# SCH_RK86_power_2024-10-30.net
KiCad netlist of a schematic drawn in EasyEDA
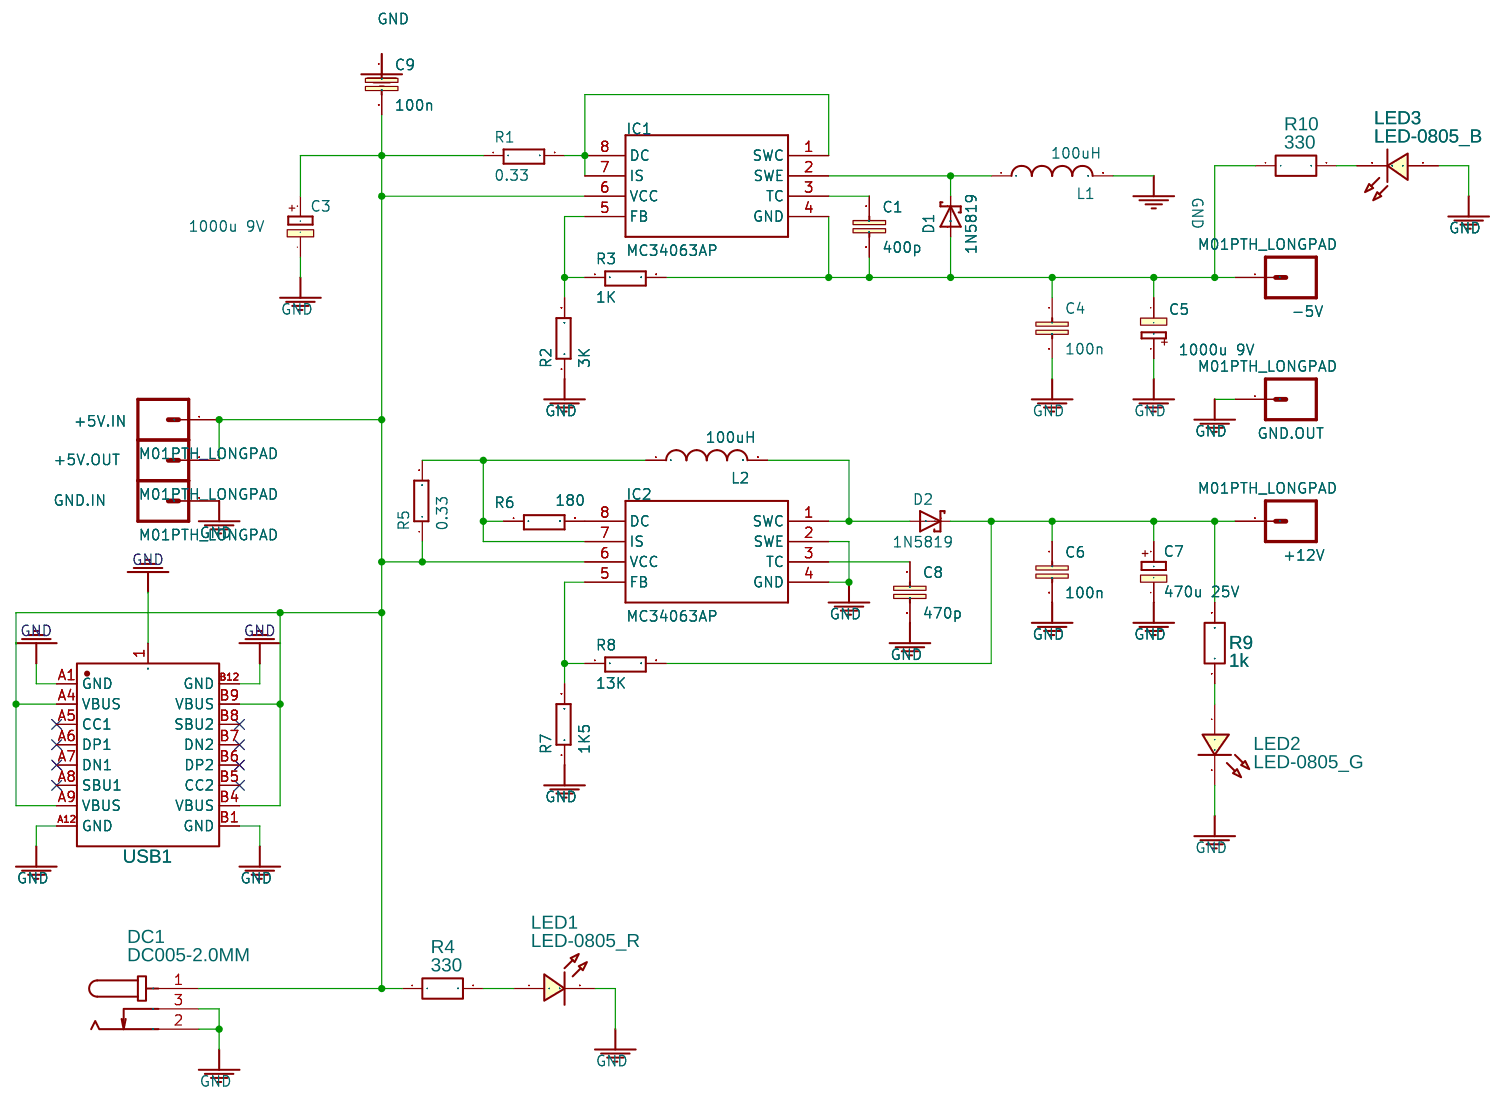
[diagram p0: schematic sheet]

(export (version "E")
  (design (tool "Eeschema 10.0.6"))
  (components
    (comp (ref "+5V.IN") (value "M01PTH_LONGPAD") (libsource (lib "") (part "Unknown_-110_-160")))
    (comp (ref "+5V.OUT") (value "M01PTH_LONGPAD") (libsource (lib "") (part "Unknown_-110_-140")))
    (comp (ref "+12V") (value "M01PTH_LONGPAD") (libsource (lib "") (part "Unknown_450_-110")))
    (comp (ref "-5V") (value "M01PTH_LONGPAD") (libsource (lib "") (part "Unknown_450_-230")))
    (comp (ref "C1") (value "400p") (libsource (lib "") (part "Unknown_240_-260")))
    (comp (ref "C3") (value "1000u 9V") (libsource (lib "") (part "Unknown_-40_-260")))
    (comp (ref "C4") (value "100n") (libsource (lib "") (part "Unknown_330_-210")))
    (comp (ref "C5") (value "1000u 9V") (libsource (lib "") (part "Unknown_380_-200")))
    (comp (ref "C6") (value "100n") (libsource (lib "") (part "Unknown_330_-90")))
    (comp (ref "C7") (value "470u 25V") (libsource (lib "") (part "Unknown_380_-90")))
    (comp (ref "C8") (value "470p") (libsource (lib "") (part "Unknown_260_-80")))
    (comp (ref "C9") (value "100n") (libsource (lib "") (part "Unknown_0_-330")))
    (comp (ref "D1") (value "1N5819") (libsource (lib "") (part "Unknown_280_-260")))
    (comp (ref "D2") (value "1N5819") (libsource (lib "") (part "Unknown_270_-110")))
    (comp (ref "DC1")
      (value "DC005-2.0MM")
      (fields (field (name "Manufacturer Part") "DC005-T20") (field (name "Manufacturer") "SOFNG(硕方)"))
      (libsource (lib "") (part "DC005-2.0MM"))
    )
    (comp (ref "GND.IN") (value "M01PTH_LONGPAD") (libsource (lib "") (part "Unknown_-110_-120")))
    (comp (ref "GND.OUT") (value "M01PTH_LONGPAD") (libsource (lib "") (part "Unknown_450_-170")))
    (comp (ref "IC1") (value "MC34063AP") (libsource (lib "") (part "Unknown_160_-290")))
    (comp (ref "IC2") (value "MC34063AP") (libsource (lib "") (part "Unknown_160_-110")))
    (comp (ref "L1") (value "100uH") (libsource (lib "") (part "Unknown_330_-280")))
    (comp (ref "L2") (value "100uH") (libsource (lib "") (part "Unknown_160_-140")))
    (comp (ref "LED1")
      (value "LED-0805_R")
      (fields
        (field (name "Manufacturer Part") "17-21SURC/S530-A3/TR8")
        (field (name "Manufacturer") "EVERLIGHT(台湾亿光)")
      )
      (libsource (lib "") (part "LED-0805_R"))
    )
    (comp (ref "LED2")
      (value "LED-0805_G")
      (fields (field (name "Manufacturer Part") "NCD0805G1") (field (name "Manufacturer") "国星光电"))
      (libsource (lib "") (part "LED-0805_G"))
    )
    (comp (ref "LED3")
      (value "LED-0805_B")
      (fields (field (name "Manufacturer Part") "D-B080508B1-KS2") (field (name "Manufacturer") "方舟 ARKLED"))
      (libsource (lib "") (part "LED-0805_B"))
    )
    (comp (ref "R1") (value "0.33") (libsource (lib "") (part "Unknown_70_-290")))
    (comp (ref "R2") (value "3K") (libsource (lib "") (part "Unknown_90_-200")))
    (comp (ref "R3") (value "1K") (libsource (lib "") (part "Unknown_120_-230")))
    (comp (ref "R4") (value "330") (libsource (lib "") (part "R_0805_EU_1")))
    (comp (ref "R5") (value "0.33") (libsource (lib "") (part "Unknown_20_-120")))
    (comp (ref "R6") (value "180") (libsource (lib "") (part "Unknown_80_-110")))
    (comp (ref "R7") (value "1K5") (libsource (lib "") (part "Unknown_90_-10")))
    (comp (ref "R8") (value "13K") (libsource (lib "") (part "Unknown_120_-40")))
    (comp (ref "R9") (value "1k") (libsource (lib "") (part "R_0805_EU")))
    (comp (ref "R10") (value "330") (libsource (lib "") (part "R_1206_EU")))
    (comp (ref "USB1")
      (value "TYPE-C-2.0-16PIN-SMT-3")
      (fields (field (name "Manufacturer") "CIKI(皓富)"))
      (libsource (lib "") (part "TYPE-C-2.0-16PIN-SMT-3"))
    )
  )
  (nets
    (net (code "1") (name "GND") (class "Default")
      (node (ref "C3") (pin "-") (pinfunction "-_-") (pintype "bidirectional"))
      (node (ref "C4") (pin "2") (pinfunction "2_2") (pintype "bidirectional"))
      (node (ref "C5") (pin "+") (pinfunction "+_+") (pintype "bidirectional"))
      (node (ref "C6") (pin "2") (pinfunction "2_2") (pintype "bidirectional"))
      (node (ref "C7") (pin "-") (pinfunction "-_-") (pintype "bidirectional"))
      (node (ref "C8") (pin "2") (pinfunction "2_2") (pintype "bidirectional"))
      (node (ref "C9") (pin "1") (pinfunction "1_1") (pintype "bidirectional"))
      (node (ref "DC1") (pin "2") (pinfunction "2_2") (pintype "unspecified"))
      (node (ref "DC1") (pin "3") (pinfunction "3_3") (pintype "unspecified"))
      (node (ref "GND.IN") (pin "1") (pinfunction "1_1") (pintype "bidirectional"))
      (node (ref "GND.OUT") (pin "1") (pinfunction "1_1") (pintype "bidirectional"))
      (node (ref "IC2") (pin "2") (pinfunction "SWE_2") (pintype "bidirectional"))
      (node (ref "IC2") (pin "4") (pinfunction "GND_4") (pintype "bidirectional"))
      (node (ref "L1") (pin "2") (pinfunction "2_2") (pintype "bidirectional"))
      (node (ref "LED1") (pin "2") (pinfunction "2_2") (pintype "unspecified"))
      (node (ref "LED2") (pin "2") (pinfunction "2_2") (pintype "unspecified"))
      (node (ref "LED3") (pin "1") (pinfunction "1_1") (pintype "unspecified"))
      (node (ref "R2") (pin "1") (pinfunction "1_1") (pintype "bidirectional"))
      (node (ref "R7") (pin "1") (pinfunction "1_1") (pintype "bidirectional"))
      (node (ref "USB1") (pin "1") (pinfunction "EH_1") (pintype "unspecified"))
      (node (ref "USB1") (pin "A1") (pinfunction "GND_A1") (pintype "unspecified"))
      (node (ref "USB1") (pin "A12") (pinfunction "GND_A12") (pintype "unspecified"))
      (node (ref "USB1") (pin "B1") (pinfunction "GND_B1") (pintype "unspecified"))
      (node (ref "USB1") (pin "B12") (pinfunction "GND_B12") (pintype "unspecified"))
    )
    (net (code "2") (name "Net-(D1-A)") (class "Default")
      (node (ref "-5V") (pin "1") (pinfunction "1_1") (pintype "bidirectional"))
      (node (ref "C1") (pin "2") (pinfunction "2_2") (pintype "bidirectional"))
      (node (ref "C4") (pin "1") (pinfunction "1_1") (pintype "bidirectional"))
      (node (ref "C5") (pin "-") (pinfunction "-_-") (pintype "bidirectional"))
      (node (ref "D1") (pin "1") (pinfunction "A_1") (pintype "bidirectional"))
      (node (ref "IC1") (pin "4") (pinfunction "GND_4") (pintype "bidirectional"))
      (node (ref "R10") (pin "1") (pinfunction "1_1") (pintype "unspecified"))
      (node (ref "R3") (pin "2") (pinfunction "2_2") (pintype "bidirectional"))
    )
    (net (code "3") (name "Net-(D1-C)") (class "Default")
      (node (ref "D1") (pin "2") (pinfunction "C_2") (pintype "bidirectional"))
      (node (ref "IC1") (pin "2") (pinfunction "SWE_2") (pintype "bidirectional"))
      (node (ref "L1") (pin "1") (pinfunction "1_1") (pintype "bidirectional"))
    )
    (net (code "4") (name "Net-(D2-A)") (class "Default")
      (node (ref "D2") (pin "1") (pinfunction "A_1") (pintype "bidirectional"))
      (node (ref "IC2") (pin "1") (pinfunction "SWC_1") (pintype "bidirectional"))
      (node (ref "L2") (pin "2") (pinfunction "2_2") (pintype "bidirectional"))
    )
    (net (code "5") (name "Net-(D2-C)") (class "Default")
      (node (ref "+12V") (pin "1") (pinfunction "1_1") (pintype "bidirectional"))
      (node (ref "C6") (pin "1") (pinfunction "1_1") (pintype "bidirectional"))
      (node (ref "C7") (pin "+") (pinfunction "+_+") (pintype "bidirectional"))
      (node (ref "D2") (pin "2") (pinfunction "C_2") (pintype "bidirectional"))
      (node (ref "R8") (pin "2") (pinfunction "2_2") (pintype "bidirectional"))
      (node (ref "R9") (pin "2") (pinfunction "2_2") (pintype "unspecified"))
    )
    (net (code "6") (name "Net-(IC1-DC)") (class "Default")
      (node (ref "IC1") (pin "1") (pinfunction "SWC_1") (pintype "bidirectional"))
      (node (ref "IC1") (pin "7") (pinfunction "IS_7") (pintype "bidirectional"))
      (node (ref "IC1") (pin "8") (pinfunction "DC_8") (pintype "bidirectional"))
      (node (ref "R1") (pin "2") (pinfunction "2_2") (pintype "bidirectional"))
    )
    (net (code "7") (name "Net-(IC1-FB)") (class "Default")
      (node (ref "IC1") (pin "5") (pinfunction "FB_5") (pintype "bidirectional"))
      (node (ref "R2") (pin "2") (pinfunction "2_2") (pintype "bidirectional"))
      (node (ref "R3") (pin "1") (pinfunction "1_1") (pintype "bidirectional"))
    )
    (net (code "8") (name "Net-(IC1-TC)") (class "Default")
      (node (ref "C1") (pin "1") (pinfunction "1_1") (pintype "bidirectional"))
      (node (ref "IC1") (pin "3") (pinfunction "TC_3") (pintype "bidirectional"))
    )
    (net (code "9") (name "Net-(IC1-VCC)") (class "Default")
      (node (ref "+5V.IN") (pin "1") (pinfunction "1_1") (pintype "bidirectional"))
      (node (ref "+5V.OUT") (pin "1") (pinfunction "1_1") (pintype "bidirectional"))
      (node (ref "C3") (pin "+") (pinfunction "+_+") (pintype "bidirectional"))
      (node (ref "C9") (pin "2") (pinfunction "2_2") (pintype "bidirectional"))
      (node (ref "DC1") (pin "1") (pinfunction "1_1") (pintype "unspecified"))
      (node (ref "IC1") (pin "6") (pinfunction "VCC_6") (pintype "bidirectional"))
      (node (ref "IC2") (pin "6") (pinfunction "VCC_6") (pintype "bidirectional"))
      (node (ref "R1") (pin "1") (pinfunction "1_1") (pintype "bidirectional"))
      (node (ref "R4") (pin "1") (pinfunction "1_1") (pintype "unspecified"))
      (node (ref "R5") (pin "1") (pinfunction "1_1") (pintype "bidirectional"))
      (node (ref "USB1") (pin "A4") (pinfunction "VBUS_A4") (pintype "unspecified"))
      (node (ref "USB1") (pin "A9") (pinfunction "VBUS_A9") (pintype "unspecified"))
      (node (ref "USB1") (pin "B4") (pinfunction "VBUS_B4") (pintype "unspecified"))
      (node (ref "USB1") (pin "B9") (pinfunction "VBUS_B9") (pintype "unspecified"))
    )
    (net (code "10") (name "Net-(IC2-DC)") (class "Default")
      (node (ref "IC2") (pin "8") (pinfunction "DC_8") (pintype "bidirectional"))
      (node (ref "R6") (pin "2") (pinfunction "2_2") (pintype "bidirectional"))
    )
    (net (code "11") (name "Net-(IC2-FB)") (class "Default")
      (node (ref "IC2") (pin "5") (pinfunction "FB_5") (pintype "bidirectional"))
      (node (ref "R7") (pin "2") (pinfunction "2_2") (pintype "bidirectional"))
      (node (ref "R8") (pin "1") (pinfunction "1_1") (pintype "bidirectional"))
    )
    (net (code "12") (name "Net-(IC2-IS)") (class "Default")
      (node (ref "IC2") (pin "7") (pinfunction "IS_7") (pintype "bidirectional"))
      (node (ref "L2") (pin "1") (pinfunction "1_1") (pintype "bidirectional"))
      (node (ref "R5") (pin "2") (pinfunction "2_2") (pintype "bidirectional"))
      (node (ref "R6") (pin "1") (pinfunction "1_1") (pintype "bidirectional"))
    )
    (net (code "13") (name "Net-(IC2-TC)") (class "Default")
      (node (ref "C8") (pin "1") (pinfunction "1_1") (pintype "bidirectional"))
      (node (ref "IC2") (pin "3") (pinfunction "TC_3") (pintype "bidirectional"))
    )
    (net (code "14") (name "Net-(LED1-Pad1)") (class "Default")
      (node (ref "LED1") (pin "1") (pinfunction "1_1") (pintype "unspecified"))
      (node (ref "R4") (pin "2") (pinfunction "2_2") (pintype "unspecified"))
    )
    (net (code "15") (name "Net-(LED2-Pad1)") (class "Default")
      (node (ref "LED2") (pin "1") (pinfunction "1_1") (pintype "unspecified"))
      (node (ref "R9") (pin "1") (pinfunction "1_1") (pintype "unspecified"))
    )
    (net (code "16") (name "Net-(LED3-Pad2)") (class "Default")
      (node (ref "LED3") (pin "2") (pinfunction "2_2") (pintype "unspecified"))
      (node (ref "R10") (pin "2") (pinfunction "2_2") (pintype "unspecified"))
    )
    (net (code "17") (name "unconnected-(USB1-CC1-PadA5)") (class "Default")
      (node (ref "USB1") (pin "A5") (pinfunction "CC1_A5") (pintype "unspecified+no_connect"))
    )
    (net (code "18") (name "unconnected-(USB1-CC2-PadB5)") (class "Default")
      (node (ref "USB1") (pin "B5") (pinfunction "CC2_B5") (pintype "unspecified+no_connect"))
    )
    (net (code "19") (name "unconnected-(USB1-DN1-PadA7)") (class "Default")
      (node (ref "USB1") (pin "A7") (pinfunction "DN1_A7") (pintype "unspecified+no_connect"))
    )
    (net (code "20") (name "unconnected-(USB1-DN2-PadB7)") (class "Default")
      (node (ref "USB1") (pin "B7") (pinfunction "DN2_B7") (pintype "unspecified+no_connect"))
    )
    (net (code "21") (name "unconnected-(USB1-DP1-PadA6)") (class "Default")
      (node (ref "USB1") (pin "A6") (pinfunction "DP1_A6") (pintype "unspecified+no_connect"))
    )
    (net (code "22") (name "unconnected-(USB1-DP2-PadB6)") (class "Default")
      (node (ref "USB1") (pin "B6") (pinfunction "DP2_B6") (pintype "unspecified+no_connect"))
    )
    (net (code "23") (name "unconnected-(USB1-SBU1-PadA8)") (class "Default")
      (node (ref "USB1") (pin "A8") (pinfunction "SBU1_A8") (pintype "unspecified+no_connect"))
    )
    (net (code "24") (name "unconnected-(USB1-SBU2-PadB8)") (class "Default")
      (node (ref "USB1") (pin "B8") (pinfunction "SBU2_B8") (pintype "unspecified+no_connect"))
    )
  )
)
